# Tractive_System_Active_Light_rev2.net
KiCad netlist of a schematic drawn in EAGLE
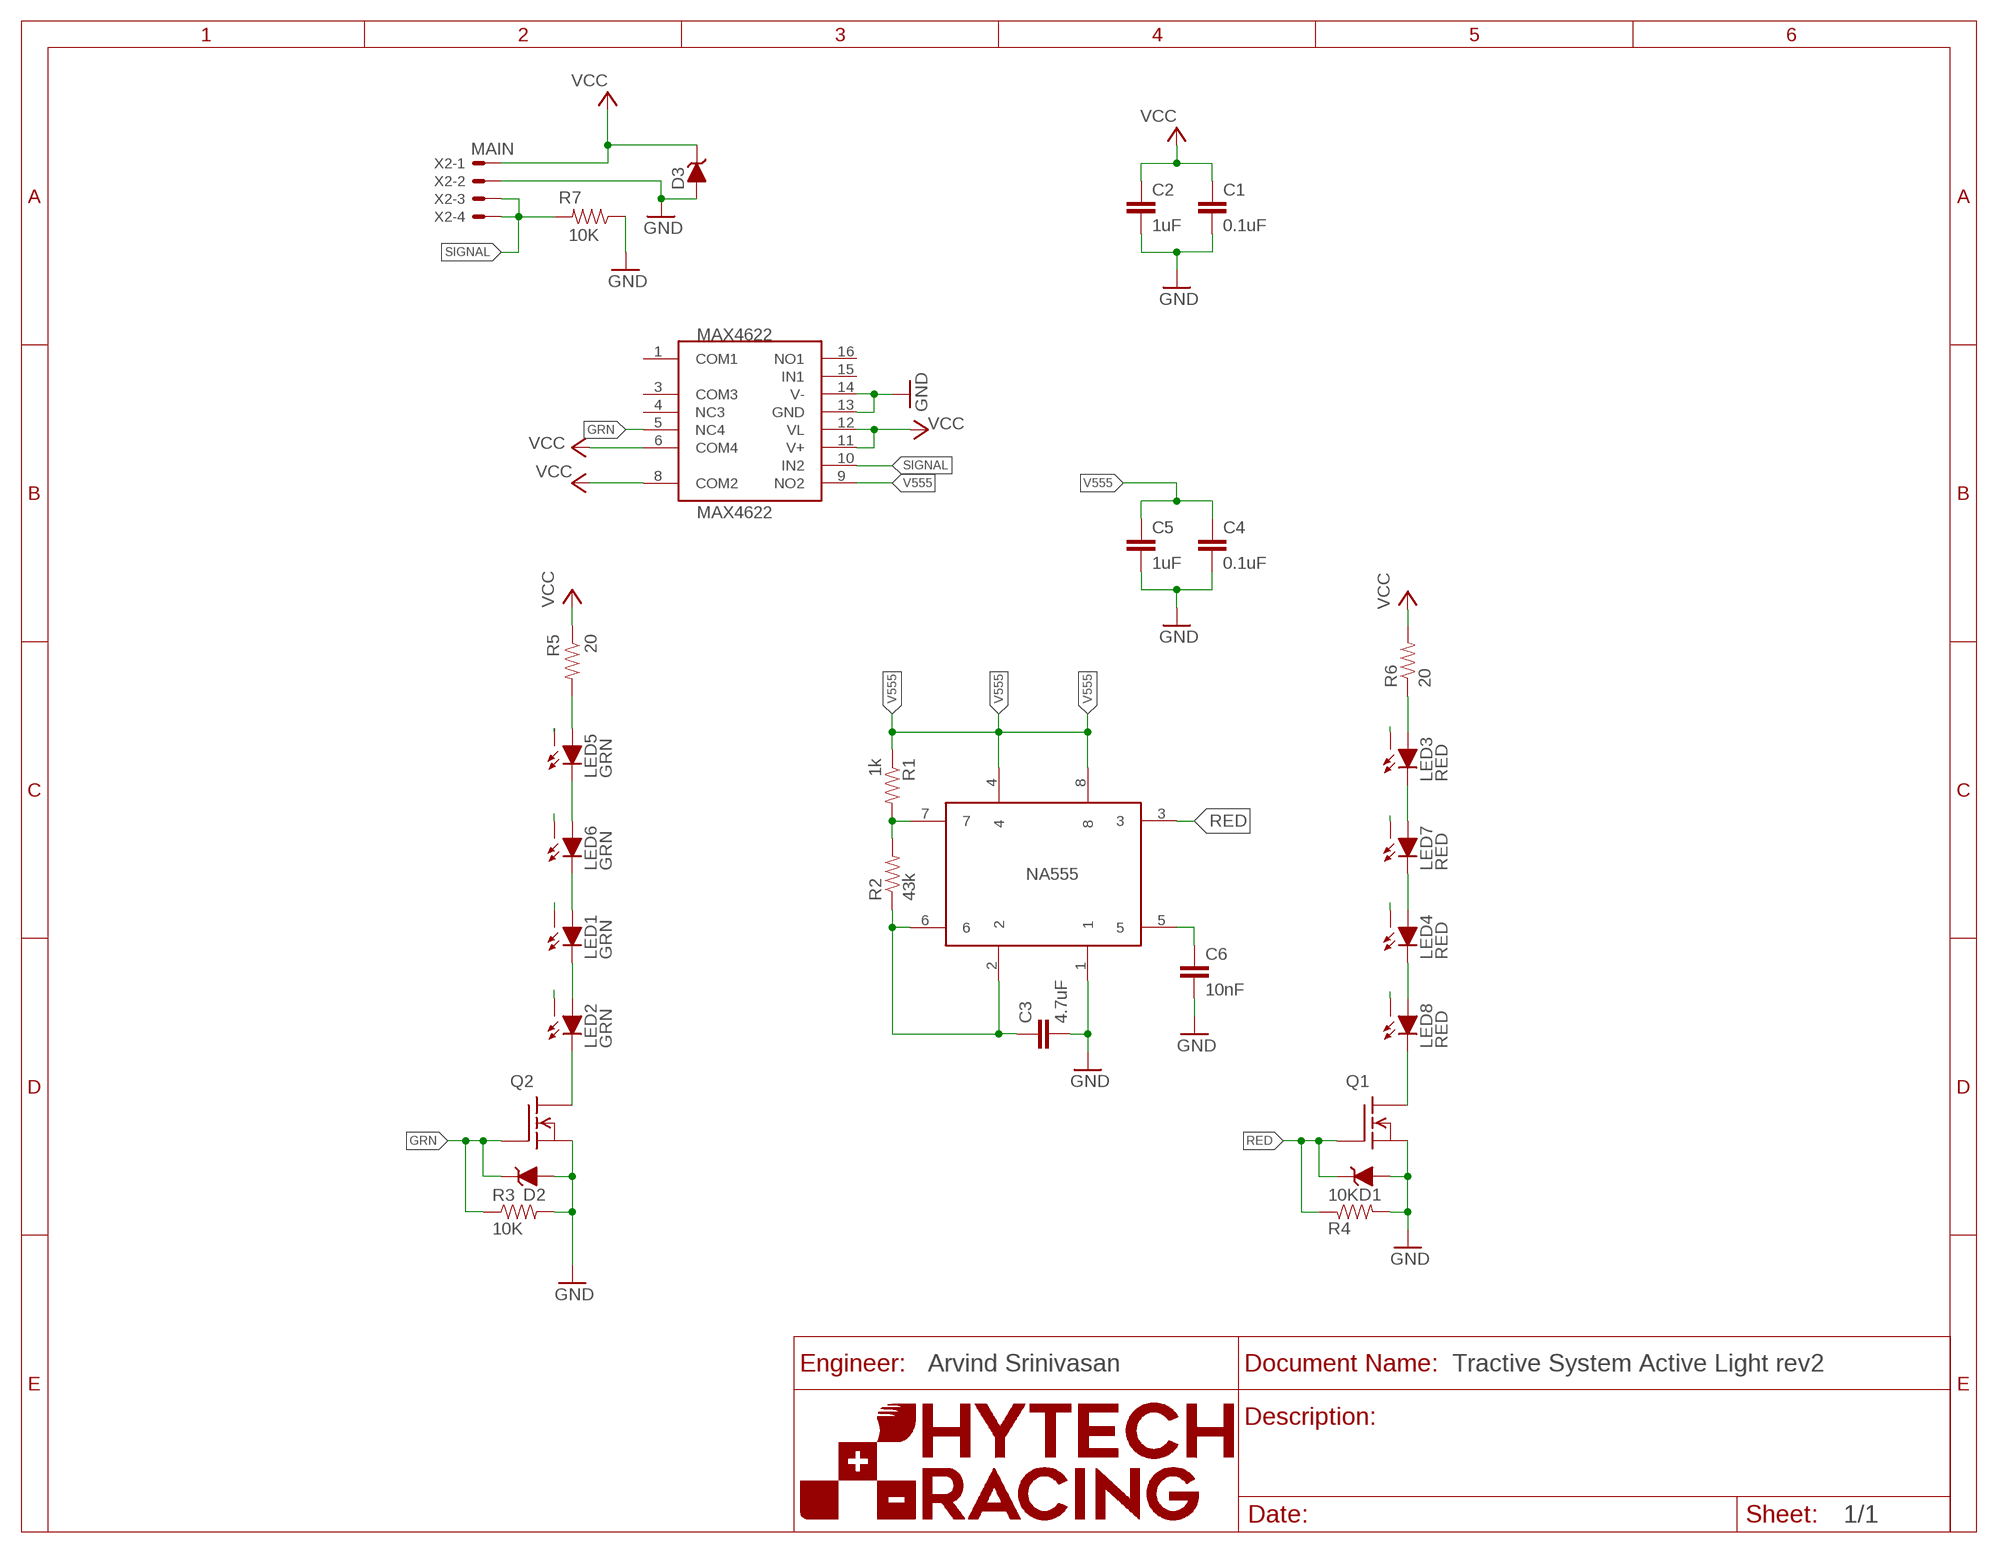
[diagram p0: schematic, sheet 1]

(export (version "E")
  (design (tool "Eeschema 10.0.6"))
  (components
    (comp (ref "C1")
      (value "0.1uF")
      (footprint "eagle-import:0603-CAP")
      (fields (field (name "TOLERANCE") "5%") (field (name "VOLTAGE") "25V"))
      (libsource (lib "eagle-import") (part "CAP0603-CAP"))
    )
    (comp (ref "C2")
      (value "1uF")
      (footprint "eagle-import:0603-CAP")
      (fields (field (name "TOLERANCE") "5%") (field (name "VOLTAGE") "25V"))
      (libsource (lib "eagle-import") (part "CAP0603-CAP"))
    )
    (comp (ref "C3")
      (value "4.7uF")
      (footprint "eagle-import:0603-CAP")
      (fields (field (name "TOLERANCE") "5%") (field (name "VOLTAGE") "25V"))
      (libsource (lib "eagle-import") (part "CAP0603-CAP"))
    )
    (comp (ref "C4")
      (value "0.1uF")
      (footprint "eagle-import:0603-CAP")
      (fields (field (name "TOLERANCE") "5%") (field (name "VOLTAGE") "25V"))
      (libsource (lib "eagle-import") (part "CAP0603-CAP"))
    )
    (comp (ref "C5")
      (value "1uF")
      (footprint "eagle-import:0603-CAP")
      (fields (field (name "TOLERANCE") "5%") (field (name "VOLTAGE") "25V"))
      (libsource (lib "eagle-import") (part "CAP0603-CAP"))
    )
    (comp (ref "C6")
      (value "10nF")
      (footprint "eagle-import:0603-CAP")
      (fields (field (name "TOLERANCE") "5%") (field (name "VOLTAGE") "25V"))
      (libsource (lib "eagle-import") (part "CAP0603-CAP"))
    )
    (comp (ref "D1")
      (value "DIODE_ZENER")
      (footprint "eagle-import:SOT23")
      (libsource (lib "eagle-import") (part "DIODE_ZENER"))
    )
    (comp (ref "D2")
      (value "DIODE_ZENER")
      (footprint "eagle-import:SOT23")
      (libsource (lib "eagle-import") (part "DIODE_ZENER"))
    )
    (comp (ref "D3")
      (value "DIODE_ZENER0603")
      (footprint "eagle-import:0603_D")
      (libsource (lib "eagle-import") (part "DIODE_ZENER0603"))
    )
    (comp (ref "LED1")
      (value "GRN")
      (footprint "eagle-import:XP-E2")
      (libsource (lib "eagle-import") (part "XP-E2XP-E2"))
    )
    (comp (ref "LED2")
      (value "GRN")
      (footprint "eagle-import:XP-E2")
      (libsource (lib "eagle-import") (part "XP-E2XP-E2"))
    )
    (comp (ref "LED3")
      (value "RED")
      (footprint "eagle-import:XP-E2")
      (libsource (lib "eagle-import") (part "XP-E2XP-E2"))
    )
    (comp (ref "LED4")
      (value "RED")
      (footprint "eagle-import:XP-E2")
      (libsource (lib "eagle-import") (part "XP-E2XP-E2"))
    )
    (comp (ref "LED5")
      (value "GRN")
      (footprint "eagle-import:XP-E2")
      (libsource (lib "eagle-import") (part "XP-E2XP-E2"))
    )
    (comp (ref "LED6")
      (value "GRN")
      (footprint "eagle-import:XP-E2")
      (libsource (lib "eagle-import") (part "XP-E2XP-E2"))
    )
    (comp (ref "LED7")
      (value "RED")
      (footprint "eagle-import:XP-E2")
      (libsource (lib "eagle-import") (part "XP-E2XP-E2"))
    )
    (comp (ref "LED8")
      (value "RED")
      (footprint "eagle-import:XP-E2")
      (libsource (lib "eagle-import") (part "XP-E2XP-E2"))
    )
    (comp (ref "MAX4622")
      (value "MAX4622")
      (footprint "eagle-import:SO16")
      (libsource (lib "eagle-import") (part "MAX4622"))
    )
    (comp (ref "NA555")
      (value "NA555SO-8")
      (footprint "eagle-import:SOIC-08")
      (libsource (lib "eagle-import") (part "NA555SO-8"))
    )
    (comp (ref "Q1")
      (value "DMG3406LSOT")
      (footprint "eagle-import:SOT23")
      (libsource (lib "eagle-import") (part "DMG3406LSOT"))
    )
    (comp (ref "Q2")
      (value "DMG3406LSOT")
      (footprint "eagle-import:SOT23")
      (libsource (lib "eagle-import") (part "DMG3406LSOT"))
    )
    (comp (ref "R1")
      (value "1k")
      (footprint "eagle-import:0603-RES")
      (fields (field (name "TOLERANCE") "1%"))
      (libsource (lib "eagle-import") (part "RESISTOR0603-RES"))
    )
    (comp (ref "R2")
      (value "43k")
      (footprint "eagle-import:0603-RES")
      (fields (field (name "TOLERANCE") "1%"))
      (libsource (lib "eagle-import") (part "RESISTOR0603-RES"))
    )
    (comp (ref "R3")
      (value "10K")
      (footprint "eagle-import:0603-RES")
      (fields (field (name "TOLERANCE") "1%"))
      (libsource (lib "eagle-import") (part "RESISTOR0603-RES"))
    )
    (comp (ref "R4")
      (value "10K")
      (footprint "eagle-import:0603-RES")
      (fields (field (name "TOLERANCE") "1%"))
      (libsource (lib "eagle-import") (part "RESISTOR0603-RES"))
    )
    (comp (ref "R5")
      (value "20")
      (footprint "eagle-import:0603-RES")
      (fields (field (name "TOLERANCE") "1%"))
      (libsource (lib "eagle-import") (part "RESISTOR0603-RES"))
    )
    (comp (ref "R6")
      (value "20")
      (footprint "eagle-import:0603-RES")
      (fields (field (name "TOLERANCE") "1%"))
      (libsource (lib "eagle-import") (part "RESISTOR0603-RES"))
    )
    (comp (ref "R7")
      (value "10K")
      (footprint "eagle-import:0603-RES")
      (fields (field (name "TOLERANCE") "1%"))
      (libsource (lib "eagle-import") (part "RESISTOR0603-RES"))
    )
    (comp (ref "X2")
      (value "MAIN")
      (footprint "eagle-import:NANO-FIT_RIGHT_ANGLE-4-SURFACE")
      (libsource (lib "eagle-import") (part "CONNECTOR-4NANO-FIT_RIGHT_ANGLE-4-SURFACE"))
    )
  )
  (nets
    (net (code "1") (name "/THERM") (class "Default")
      (node (ref "LED1") (pin "X") (pinfunction "X_X") (pintype "passive"))
      (node (ref "LED2") (pin "X") (pinfunction "X_X") (pintype "passive"))
      (node (ref "LED3") (pin "X") (pinfunction "X_X") (pintype "passive"))
      (node (ref "LED4") (pin "X") (pinfunction "X_X") (pintype "passive"))
      (node (ref "LED5") (pin "X") (pinfunction "X_X") (pintype "passive"))
      (node (ref "LED6") (pin "X") (pinfunction "X_X") (pintype "passive"))
      (node (ref "LED7") (pin "X") (pinfunction "X_X") (pintype "passive"))
      (node (ref "LED8") (pin "X") (pinfunction "X_X") (pintype "passive"))
    )
    (net (code "2") (name "GND") (class "Default")
      (node (ref "C1") (pin "2") (pinfunction "2_2") (pintype "passive"))
      (node (ref "C2") (pin "2") (pinfunction "2_2") (pintype "passive"))
      (node (ref "C3") (pin "2") (pinfunction "2_2") (pintype "passive"))
      (node (ref "C4") (pin "2") (pinfunction "2_2") (pintype "passive"))
      (node (ref "C5") (pin "2") (pinfunction "2_2") (pintype "passive"))
      (node (ref "C6") (pin "2") (pinfunction "2_2") (pintype "passive"))
      (node (ref "D1") (pin "1") (pinfunction "A_1") (pintype "passive"))
      (node (ref "D2") (pin "1") (pinfunction "A_1") (pintype "passive"))
      (node (ref "D3") (pin "A") (pinfunction "A_A") (pintype "passive"))
      (node (ref "MAX4622") (pin "13") (pinfunction "GND_13") (pintype "bidirectional"))
      (node (ref "MAX4622") (pin "14") (pinfunction "V-_14") (pintype "bidirectional"))
      (node (ref "NA555") (pin "1") (pinfunction "1_1") (pintype "bidirectional"))
      (node (ref "Q1") (pin "2") (pinfunction "S_2") (pintype "passive"))
      (node (ref "Q2") (pin "2") (pinfunction "S_2") (pintype "passive"))
      (node (ref "R3") (pin "2") (pinfunction "2_2") (pintype "passive"))
      (node (ref "R4") (pin "2") (pinfunction "2_2") (pintype "passive"))
      (node (ref "R7") (pin "1") (pinfunction "1_1") (pintype "passive"))
      (node (ref "X2") (pin "2") (pinfunction "S_2") (pintype "passive"))
    )
    (net (code "3") (name "GRN") (class "Default")
      (node (ref "D2") (pin "3") (pinfunction "C_3") (pintype "passive"))
      (node (ref "MAX4622") (pin "5") (pinfunction "NC4_5") (pintype "bidirectional"))
      (node (ref "Q2") (pin "1") (pinfunction "G_1") (pintype "passive"))
      (node (ref "R3") (pin "1") (pinfunction "1_1") (pintype "passive"))
    )
    (net (code "4") (name "Net-(C3-Pad1)") (class "Default")
      (node (ref "C3") (pin "1") (pinfunction "1_1") (pintype "passive"))
      (node (ref "NA555") (pin "2") (pinfunction "2_2") (pintype "bidirectional"))
      (node (ref "NA555") (pin "6") (pinfunction "6_6") (pintype "bidirectional"))
      (node (ref "R2") (pin "1") (pinfunction "1_1") (pintype "passive"))
    )
    (net (code "5") (name "Net-(C6-Pad1)") (class "Default")
      (node (ref "C6") (pin "1") (pinfunction "1_1") (pintype "passive"))
      (node (ref "NA555") (pin "5") (pinfunction "5_5") (pintype "bidirectional"))
    )
    (net (code "6") (name "Net-(LED1-PadA)") (class "Default")
      (node (ref "LED1") (pin "A") (pinfunction "A_A") (pintype "passive"))
      (node (ref "LED6") (pin "C") (pinfunction "C_C") (pintype "passive"))
    )
    (net (code "7") (name "Net-(LED1-PadC)") (class "Default")
      (node (ref "LED1") (pin "C") (pinfunction "C_C") (pintype "passive"))
      (node (ref "LED2") (pin "A") (pinfunction "A_A") (pintype "passive"))
    )
    (net (code "8") (name "Net-(LED3-PadA)") (class "Default")
      (node (ref "LED3") (pin "A") (pinfunction "A_A") (pintype "passive"))
      (node (ref "R6") (pin "1") (pinfunction "1_1") (pintype "passive"))
    )
    (net (code "9") (name "Net-(LED3-PadC)") (class "Default")
      (node (ref "LED3") (pin "C") (pinfunction "C_C") (pintype "passive"))
      (node (ref "LED7") (pin "A") (pinfunction "A_A") (pintype "passive"))
    )
    (net (code "10") (name "Net-(LED4-PadA)") (class "Default")
      (node (ref "LED4") (pin "A") (pinfunction "A_A") (pintype "passive"))
      (node (ref "LED7") (pin "C") (pinfunction "C_C") (pintype "passive"))
    )
    (net (code "11") (name "Net-(LED4-PadC)") (class "Default")
      (node (ref "LED4") (pin "C") (pinfunction "C_C") (pintype "passive"))
      (node (ref "LED8") (pin "A") (pinfunction "A_A") (pintype "passive"))
    )
    (net (code "12") (name "Net-(LED5-PadA)") (class "Default")
      (node (ref "LED5") (pin "A") (pinfunction "A_A") (pintype "passive"))
      (node (ref "R5") (pin "2") (pinfunction "2_2") (pintype "passive"))
    )
    (net (code "13") (name "Net-(LED5-PadC)") (class "Default")
      (node (ref "LED5") (pin "C") (pinfunction "C_C") (pintype "passive"))
      (node (ref "LED6") (pin "A") (pinfunction "A_A") (pintype "passive"))
    )
    (net (code "14") (name "Net-(NA555-Pad7)") (class "Default")
      (node (ref "NA555") (pin "7") (pinfunction "7_7") (pintype "bidirectional"))
      (node (ref "R1") (pin "2") (pinfunction "2_2") (pintype "passive"))
      (node (ref "R2") (pin "2") (pinfunction "2_2") (pintype "passive"))
    )
    (net (code "15") (name "Net-(Q1-D)") (class "Default")
      (node (ref "LED8") (pin "C") (pinfunction "C_C") (pintype "passive"))
      (node (ref "Q1") (pin "3") (pinfunction "D_3") (pintype "passive"))
    )
    (net (code "16") (name "Net-(Q2-D)") (class "Default")
      (node (ref "LED2") (pin "C") (pinfunction "C_C") (pintype "passive"))
      (node (ref "Q2") (pin "3") (pinfunction "D_3") (pintype "passive"))
    )
    (net (code "17") (name "RED") (class "Default")
      (node (ref "D1") (pin "3") (pinfunction "C_3") (pintype "passive"))
      (node (ref "NA555") (pin "3") (pinfunction "3_3") (pintype "bidirectional"))
      (node (ref "Q1") (pin "1") (pinfunction "G_1") (pintype "passive"))
      (node (ref "R4") (pin "1") (pinfunction "1_1") (pintype "passive"))
    )
    (net (code "18") (name "SIGNAL") (class "Default")
      (node (ref "MAX4622") (pin "10") (pinfunction "IN2_10") (pintype "bidirectional"))
      (node (ref "R7") (pin "2") (pinfunction "2_2") (pintype "passive"))
      (node (ref "X2") (pin "3") (pinfunction "S_3") (pintype "passive"))
      (node (ref "X2") (pin "4") (pinfunction "S_4") (pintype "passive"))
    )
    (net (code "19") (name "V555") (class "Default")
      (node (ref "C4") (pin "1") (pinfunction "1_1") (pintype "passive"))
      (node (ref "C5") (pin "1") (pinfunction "1_1") (pintype "passive"))
      (node (ref "MAX4622") (pin "9") (pinfunction "NO2_9") (pintype "bidirectional"))
      (node (ref "NA555") (pin "4") (pinfunction "4_4") (pintype "bidirectional"))
      (node (ref "NA555") (pin "8") (pinfunction "8_8") (pintype "bidirectional"))
      (node (ref "R1") (pin "1") (pinfunction "1_1") (pintype "passive"))
    )
    (net (code "20") (name "VCC") (class "Default")
      (node (ref "C1") (pin "1") (pinfunction "1_1") (pintype "passive"))
      (node (ref "C2") (pin "1") (pinfunction "1_1") (pintype "passive"))
      (node (ref "D3") (pin "C") (pinfunction "C_C") (pintype "passive"))
      (node (ref "MAX4622") (pin "11") (pinfunction "V+_11") (pintype "bidirectional"))
      (node (ref "MAX4622") (pin "12") (pinfunction "VL_12") (pintype "bidirectional"))
      (node (ref "MAX4622") (pin "6") (pinfunction "COM4_6") (pintype "bidirectional"))
      (node (ref "MAX4622") (pin "8") (pinfunction "COM2_8") (pintype "bidirectional"))
      (node (ref "R5") (pin "1") (pinfunction "1_1") (pintype "passive"))
      (node (ref "R6") (pin "2") (pinfunction "2_2") (pintype "passive"))
      (node (ref "X2") (pin "1") (pinfunction "S_1") (pintype "passive"))
    )
    (net (code "21") (name "unconnected-(MAX4622-COM1-Pad1)") (class "Default")
      (node (ref "MAX4622") (pin "1") (pinfunction "COM1_1") (pintype "bidirectional"))
    )
    (net (code "22") (name "unconnected-(MAX4622-COM3-Pad3)") (class "Default")
      (node (ref "MAX4622") (pin "3") (pinfunction "COM3_3") (pintype "bidirectional"))
    )
    (net (code "23") (name "unconnected-(MAX4622-IN1-Pad15)") (class "Default")
      (node (ref "MAX4622") (pin "15") (pinfunction "IN1_15") (pintype "bidirectional"))
    )
    (net (code "24") (name "unconnected-(MAX4622-NC3-Pad4)") (class "Default")
      (node (ref "MAX4622") (pin "4") (pinfunction "NC3_4") (pintype "bidirectional"))
    )
    (net (code "25") (name "unconnected-(MAX4622-NO1-Pad16)") (class "Default")
      (node (ref "MAX4622") (pin "16") (pinfunction "NO1_16") (pintype "bidirectional"))
    )
  )
)
